# MIDDLE_LAYER.net
KiCad netlist of a schematic drawn in Altium Designer
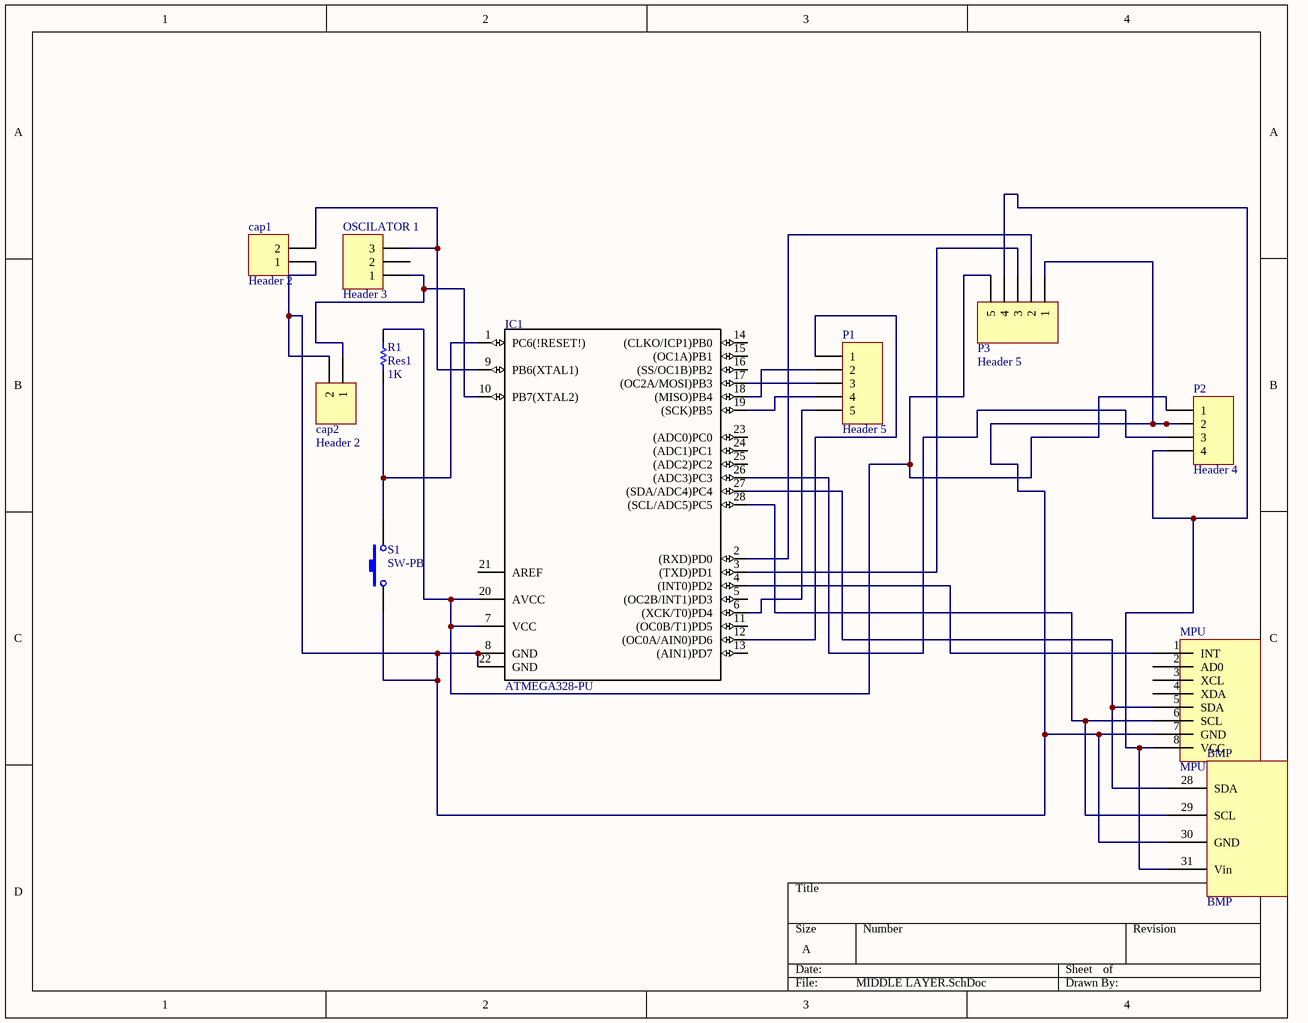
[diagram p0: MIDDLE LAYER.SchDoc]

(export (version "E")
  (design (tool "Eeschema 10.0.6"))
  (components
    (comp (ref "BMP") (value "BMP") (footprint "BMP") (libsource (lib "bmb") (part "BMP")))
    (comp (ref "cap1")
      (value "Header 2")
      (footprint "HDR1X2")
      (description "Header, 2-Pin")
      (fields (field (name "PUBLISHER") "Altium Limited"))
      (libsource (lib "Miscellaneous Connectors") (part "Header 2"))
    )
    (comp (ref "cap2")
      (value "Header 2")
      (footprint "HDR1X2")
      (description "Header, 2-Pin")
      (fields (field (name "PUBLISHER") "Altium Limited"))
      (libsource (lib "") (part "Header 2_1"))
    )
    (comp (ref "IC1")
      (value "ATMEGA328-PU")
      (footprint "*DIL28")
      (description "ATmega Series 20 MHz 32 KB Flash 2 KB SRAM 8-Bit Microcontroller - DIP-28")
      (fields (field (name "MF") "Microchip"))
      (libsource (lib "ATMEGA328-PU") (part "ATMEGA328-PU"))
    )
    (comp (ref "MPU") (value "MPU") (footprint "MPU") (libsource (lib "MPU") (part "MPU")))
    (comp (ref "OSCILATOR 1")
      (value "Header 3")
      (footprint "HDR1X3")
      (description "Header, 3-Pin")
      (fields (field (name "PUBLISHER") "Altium Limited"))
      (libsource (lib "Miscellaneous Connectors") (part "Header 3"))
    )
    (comp (ref "P1")
      (value "Header 5")
      (footprint "HDR1X5")
      (description "Header, 5-Pin")
      (fields (field (name "PUBLISHER") "Altium Limited"))
      (libsource (lib "Miscellaneous Connectors") (part "Header 5"))
    )
    (comp (ref "P2")
      (value "Header 4")
      (footprint "HDR1X4")
      (description "Header, 4-Pin")
      (fields (field (name "PUBLISHER") "Altium Limited"))
      (libsource (lib "Miscellaneous Connectors") (part "Header 4"))
    )
    (comp (ref "P3")
      (value "Header 5")
      (footprint "HDR1X5")
      (description "Header, 5-Pin")
      (fields (field (name "PUBLISHER") "Altium Limited"))
      (libsource (lib "") (part "Header 5_1"))
    )
    (comp (ref "R1")
      (value "Res1")
      (footprint "AXIAL-0.3")
      (description "Resistor")
      (fields (field (name "ALTIUM_VALUE") "1K") (field (name "PUBLISHER") "Altium Limited"))
      (libsource (lib "Miscellaneous Devices") (part "Res1"))
    )
    (comp (ref "S1")
      (value "SW-PB")
      (footprint "SPST-2")
      (description "Switch")
      (fields (field (name "PUBLISHER") "Altium Limited"))
      (libsource (lib "Miscellaneous Devices") (part "SW-PB"))
    )
  )
  (nets
    (net (code "1") (name "Net-(BMP-GND)") (class "Default")
      (node (ref "BMP") (pin "30") (pinfunction "GND_30") (pintype "passive"))
      (node (ref "IC1") (pin "22") (pinfunction "GND_22") (pintype "power_in"))
      (node (ref "IC1") (pin "8") (pinfunction "GND_8") (pintype "power_in"))
      (node (ref "MPU") (pin "7") (pinfunction "GND_7") (pintype "passive"))
      (node (ref "P2") (pin "2") (pinfunction "2_2") (pintype "passive"))
      (node (ref "P3") (pin "1") (pinfunction "1_1") (pintype "passive"))
      (node (ref "S1") (pin "1") (pinfunction "1_1") (pintype "passive"))
      (node (ref "cap1") (pin "1") (pinfunction "1_1") (pintype "passive"))
      (node (ref "cap2") (pin "2") (pinfunction "2_2") (pintype "passive"))
    )
    (net (code "2") (name "Net-(BMP-SCL)") (class "Default")
      (node (ref "BMP") (pin "29") (pinfunction "SCL_29") (pintype "passive"))
      (node (ref "IC1") (pin "28") (pinfunction "(SCL/ADC5)PC5_28") (pintype "bidirectional"))
      (node (ref "MPU") (pin "6") (pinfunction "SCL_6") (pintype "passive"))
    )
    (net (code "3") (name "Net-(BMP-SDA)") (class "Default")
      (node (ref "BMP") (pin "28") (pinfunction "SDA_28") (pintype "passive"))
      (node (ref "IC1") (pin "27") (pinfunction "(SDA/ADC4)PC4_27") (pintype "bidirectional"))
      (node (ref "MPU") (pin "5") (pinfunction "SDA_5") (pintype "passive"))
    )
    (net (code "4") (name "Net-(BMP-Vin)") (class "Default")
      (node (ref "BMP") (pin "31") (pinfunction "Vin_31") (pintype "passive"))
      (node (ref "MPU") (pin "8") (pinfunction "VCC_8") (pintype "passive"))
      (node (ref "P2") (pin "4") (pinfunction "4_4") (pintype "passive"))
      (node (ref "P3") (pin "4") (pinfunction "4_4") (pintype "passive"))
    )
    (net (code "5") (name "Net-(IC1-(ADC3)PC3)") (class "Default")
      (node (ref "IC1") (pin "26") (pinfunction "(ADC3)PC3_26") (pintype "bidirectional"))
      (node (ref "P2") (pin "3") (pinfunction "3_3") (pintype "passive"))
    )
    (net (code "6") (name "Net-(IC1-(INT0)PD2)") (class "Default")
      (node (ref "IC1") (pin "4") (pinfunction "(INT0)PD2_4") (pintype "bidirectional"))
      (node (ref "MPU") (pin "1") (pinfunction "INT_1") (pintype "passive"))
    )
    (net (code "7") (name "Net-(IC1-(MISO)PB4)") (class "Default")
      (node (ref "IC1") (pin "18") (pinfunction "(MISO)PB4_18") (pintype "bidirectional"))
      (node (ref "P1") (pin "2") (pinfunction "2_2") (pintype "passive"))
    )
    (net (code "8") (name "Net-(IC1-(OC0A{slash}AIN0)PD6)") (class "Default")
      (node (ref "IC1") (pin "12") (pinfunction "(OC0A/AIN0)PD6_12") (pintype "bidirectional"))
      (node (ref "P1") (pin "1") (pinfunction "1_1") (pintype "passive"))
    )
    (net (code "9") (name "Net-(IC1-(OC2A{slash}MOSI)PB3)") (class "Default")
      (node (ref "IC1") (pin "17") (pinfunction "(OC2A/MOSI)PB3_17") (pintype "bidirectional"))
      (node (ref "P1") (pin "3") (pinfunction "3_3") (pintype "passive"))
    )
    (net (code "10") (name "Net-(IC1-(RXD)PD0)") (class "Default")
      (node (ref "IC1") (pin "2") (pinfunction "(RXD)PD0_2") (pintype "bidirectional"))
      (node (ref "P3") (pin "2") (pinfunction "2_2") (pintype "passive"))
    )
    (net (code "11") (name "Net-(IC1-(SCK)PB5)") (class "Default")
      (node (ref "IC1") (pin "19") (pinfunction "(SCK)PB5_19") (pintype "bidirectional"))
      (node (ref "P1") (pin "4") (pinfunction "4_4") (pintype "passive"))
    )
    (net (code "12") (name "Net-(IC1-(TXD)PD1)") (class "Default")
      (node (ref "IC1") (pin "3") (pinfunction "(TXD)PD1_3") (pintype "bidirectional"))
      (node (ref "P3") (pin "3") (pinfunction "3_3") (pintype "passive"))
    )
    (net (code "13") (name "Net-(IC1-(XCK{slash}T0)PD4)") (class "Default")
      (node (ref "IC1") (pin "6") (pinfunction "(XCK/T0)PD4_6") (pintype "bidirectional"))
      (node (ref "P1") (pin "5") (pinfunction "5_5") (pintype "passive"))
    )
    (net (code "14") (name "Net-(IC1-AVCC)") (class "Default")
      (node (ref "IC1") (pin "20") (pinfunction "AVCC_20") (pintype "power_in"))
      (node (ref "IC1") (pin "7") (pinfunction "VCC_7") (pintype "power_in"))
      (node (ref "P2") (pin "1") (pinfunction "1_1") (pintype "passive"))
      (node (ref "P3") (pin "5") (pinfunction "5_5") (pintype "passive"))
      (node (ref "R1") (pin "2") (pinfunction "2_2") (pintype "passive"))
    )
    (net (code "15") (name "Net-(IC1-PB6(XTAL1))") (class "Default")
      (node (ref "IC1") (pin "9") (pinfunction "PB6(XTAL1)_9") (pintype "bidirectional"))
      (node (ref "OSCILATOR 1") (pin "3") (pinfunction "3_3") (pintype "passive"))
      (node (ref "cap1") (pin "2") (pinfunction "2_2") (pintype "passive"))
    )
    (net (code "16") (name "Net-(IC1-PB7(XTAL2))") (class "Default")
      (node (ref "IC1") (pin "10") (pinfunction "PB7(XTAL2)_10") (pintype "bidirectional"))
      (node (ref "OSCILATOR 1") (pin "1") (pinfunction "1_1") (pintype "passive"))
      (node (ref "cap2") (pin "1") (pinfunction "1_1") (pintype "passive"))
    )
    (net (code "17") (name "Net-(IC1-PC6(!RESET!))") (class "Default")
      (node (ref "IC1") (pin "1") (pinfunction "PC6(!RESET!)_1") (pintype "bidirectional"))
      (node (ref "R1") (pin "1") (pinfunction "1_1") (pintype "passive"))
      (node (ref "S1") (pin "2") (pinfunction "2_2") (pintype "passive"))
    )
    (net (code "18") (name "unconnected-(IC1-(ADC0)PC0-Pad23)") (class "Default")
      (node (ref "IC1") (pin "23") (pinfunction "(ADC0)PC0_23") (pintype "bidirectional"))
    )
    (net (code "19") (name "unconnected-(IC1-(ADC1)PC1-Pad24)") (class "Default")
      (node (ref "IC1") (pin "24") (pinfunction "(ADC1)PC1_24") (pintype "bidirectional"))
    )
    (net (code "20") (name "unconnected-(IC1-(ADC2)PC2-Pad25)") (class "Default")
      (node (ref "IC1") (pin "25") (pinfunction "(ADC2)PC2_25") (pintype "bidirectional"))
    )
    (net (code "21") (name "unconnected-(IC1-(AIN1)PD7-Pad13)") (class "Default")
      (node (ref "IC1") (pin "13") (pinfunction "(AIN1)PD7_13") (pintype "bidirectional"))
    )
    (net (code "22") (name "unconnected-(IC1-(CLKO{slash}ICP1)PB0-Pad14)") (class "Default")
      (node (ref "IC1") (pin "14") (pinfunction "(CLKO/ICP1)PB0_14") (pintype "bidirectional"))
    )
    (net (code "23") (name "unconnected-(IC1-(OC0B{slash}T1)PD5-Pad11)") (class "Default")
      (node (ref "IC1") (pin "11") (pinfunction "(OC0B/T1)PD5_11") (pintype "bidirectional"))
    )
    (net (code "24") (name "unconnected-(IC1-(OC1A)PB1-Pad15)") (class "Default")
      (node (ref "IC1") (pin "15") (pinfunction "(OC1A)PB1_15") (pintype "bidirectional"))
    )
    (net (code "25") (name "unconnected-(IC1-(OC2B{slash}INT1)PD3-Pad5)") (class "Default")
      (node (ref "IC1") (pin "5") (pinfunction "(OC2B/INT1)PD3_5") (pintype "bidirectional"))
    )
    (net (code "26") (name "unconnected-(IC1-(SS{slash}OC1B)PB2-Pad16)") (class "Default")
      (node (ref "IC1") (pin "16") (pinfunction "(SS/OC1B)PB2_16") (pintype "bidirectional"))
    )
    (net (code "27") (name "unconnected-(IC1-AREF-Pad21)") (class "Default")
      (node (ref "IC1") (pin "21") (pinfunction "AREF_21") (pintype "passive"))
    )
    (net (code "28") (name "unconnected-(MPU-AD0-Pad2)") (class "Default")
      (node (ref "MPU") (pin "2") (pinfunction "AD0_2") (pintype "passive"))
    )
    (net (code "29") (name "unconnected-(MPU-XCL-Pad3)") (class "Default")
      (node (ref "MPU") (pin "3") (pinfunction "XCL_3") (pintype "passive"))
    )
    (net (code "30") (name "unconnected-(MPU-XDA-Pad4)") (class "Default")
      (node (ref "MPU") (pin "4") (pinfunction "XDA_4") (pintype "passive"))
    )
    (net (code "31") (name "unconnected-(OSCILATOR 1-Pad2)") (class "Default")
      (node (ref "OSCILATOR 1") (pin "2") (pinfunction "2_2") (pintype "passive"))
    )
  )
)
